# Canhbaochayrung.net
KiCad netlist of a schematic drawn in Altium Designer
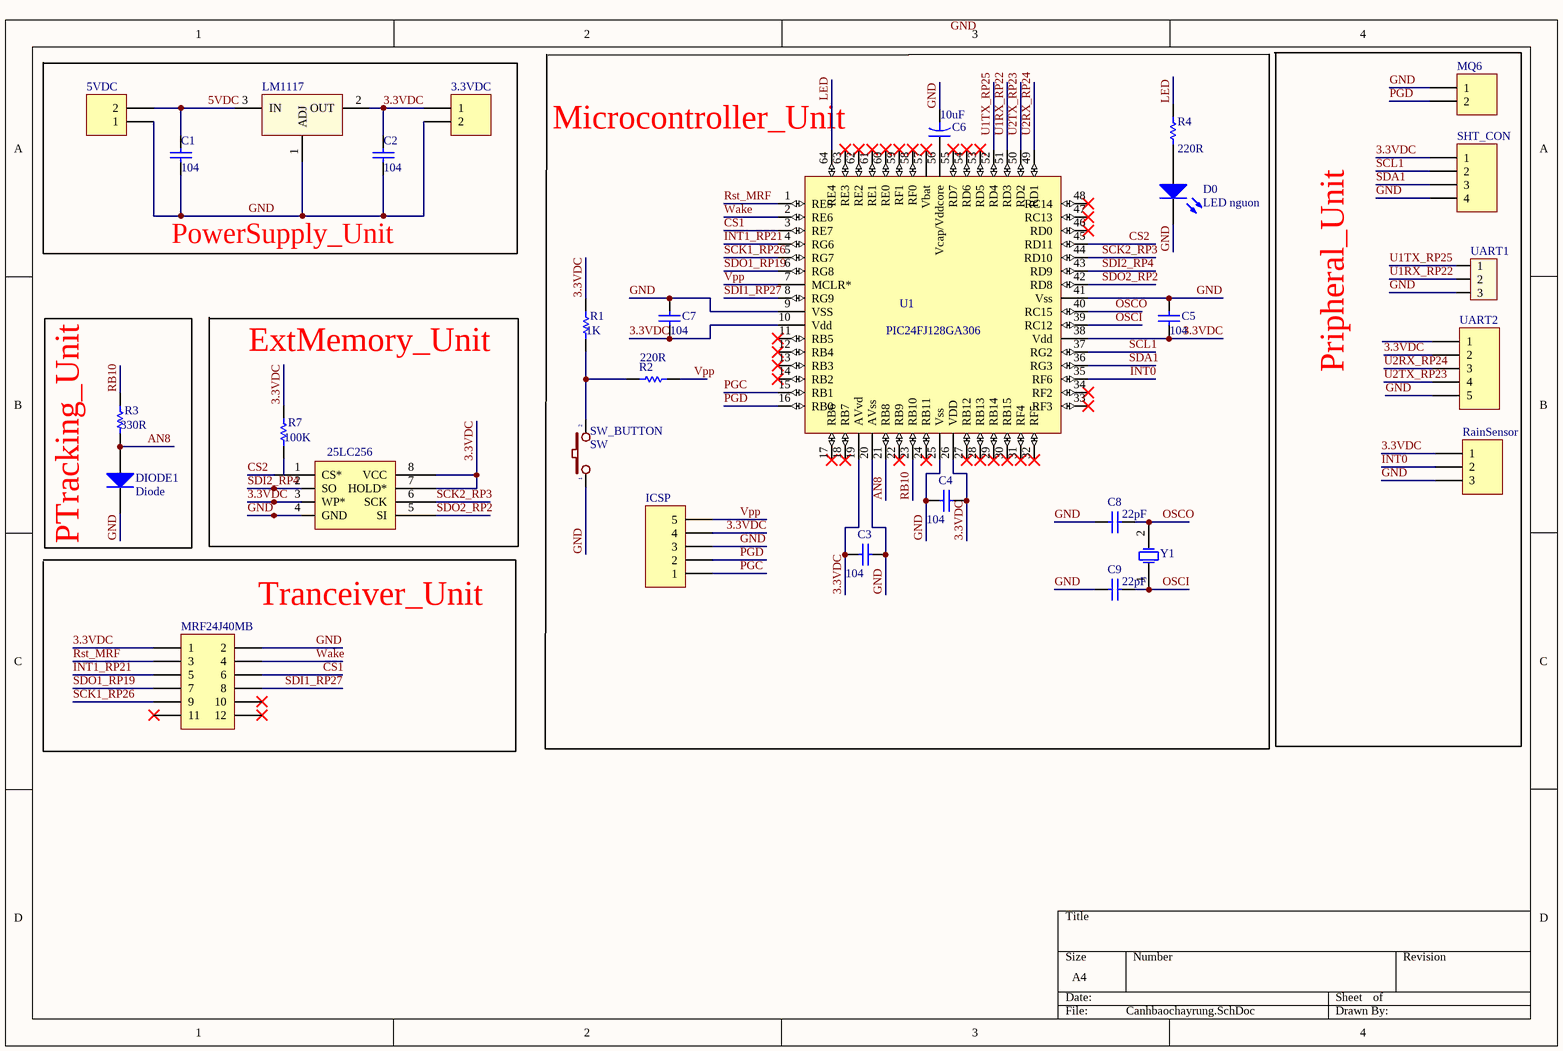
[diagram p0: Canhbaochayrung.SchDoc]

(export (version "E")
  (design (tool "Eeschema 10.0.6"))
  (components
    (comp (ref "3.3VDC")
      (value "Header 2")
      (footprint "HDR1X2")
      (description "Header, 2-Pin")
      (fields (field (name "PUBLISHER") "Altium Limited"))
      (libsource (lib "") (part "Header 2_1"))
    )
    (comp (ref "5VDC")
      (value "Header 2")
      (footprint "HDR1X2")
      (description "Header, 2-Pin")
      (fields (field (name "PUBLISHER") "Altium Limited"))
      (libsource (lib "Miscellaneous Connectors") (part "Header 2"))
    )
    (comp (ref "25LC256") (value "25LC256") (footprint "DIP-8") (libsource (lib "25LC256") (part "25LC256")))
    (comp (ref "C1")
      (value "104")
      (footprint "C0805")
      (description "Capacitor")
      (fields (field (name "Comment") "Cap") (field (name "PUBLISHER") "Altium Limited"))
      (libsource (lib "Miscellaneous Devices") (part "Cap"))
    )
    (comp (ref "C2")
      (value "104")
      (footprint "C0805")
      (description "Capacitor")
      (fields (field (name "Comment") "Cap") (field (name "PUBLISHER") "Altium Limited"))
      (libsource (lib "Miscellaneous Devices") (part "Cap"))
    )
    (comp (ref "C3")
      (value "104")
      (footprint "C0805")
      (description "Capacitor")
      (fields (field (name "Comment") "Cap") (field (name "PUBLISHER") "Altium Limited"))
      (libsource (lib "Miscellaneous Devices") (part "Cap"))
    )
    (comp (ref "C4")
      (value "104")
      (footprint "C0805")
      (description "Capacitor")
      (fields (field (name "Comment") "Cap") (field (name "PUBLISHER") "Altium Limited"))
      (libsource (lib "Miscellaneous Devices") (part "Cap"))
    )
    (comp (ref "C5")
      (value "104")
      (footprint "C0805")
      (description "Capacitor")
      (fields (field (name "Comment") "Cap") (field (name "PUBLISHER") "Altium Limited"))
      (libsource (lib "Miscellaneous Devices") (part "Cap"))
    )
    (comp (ref "C6")
      (value "10uF")
      (footprint "CAP P 6.3x5.4")
      (description "Capacitor")
      (fields (field (name "Comment") "Cap2") (field (name "PUBLISHER") "Altium Limited"))
      (libsource (lib "Miscellaneous Devices") (part "Cap2"))
    )
    (comp (ref "C7")
      (value "104")
      (footprint "C0805")
      (description "Capacitor")
      (fields (field (name "Comment") "Cap") (field (name "PUBLISHER") "Altium Limited"))
      (libsource (lib "Miscellaneous Devices") (part "Cap"))
    )
    (comp (ref "C8")
      (value "22pF")
      (footprint "SM-0805")
      (description "Capacitor")
      (fields (field (name "Comment") "Cap") (field (name "PUBLISHER") "Altium Limited"))
      (libsource (lib "Miscellaneous Devices") (part "Cap"))
    )
    (comp (ref "C9")
      (value "22pF")
      (footprint "SM-0805")
      (description "Capacitor")
      (fields (field (name "Comment") "Cap") (field (name "PUBLISHER") "Altium Limited"))
      (libsource (lib "Miscellaneous Devices") (part "Cap"))
    )
    (comp (ref "D0")
      (value "LED nguon")
      (footprint "LED3mm")
      (description "Typical INFRARED GaAs LED")
      (fields (field (name "PUBLISHER") "Altium Limited"))
      (libsource (lib "Miscellaneous Devices") (part "LED0"))
    )
    (comp (ref "DIODE1")
      (value "Diode")
      (footprint "DZ0.5A")
      (description "Default Diode")
      (fields (field (name "PUBLISHER") "Altium Limited"))
      (libsource (lib "Miscellaneous Devices") (part "Diode"))
    )
    (comp (ref "ICSP")
      (value "ICSP")
      (footprint "CON5")
      (description "Header, 5-Pin")
      (fields (field (name "PUBLISHER") "Altium Limited"))
      (libsource (lib "Miscellaneous Connectors") (part "Header 5"))
    )
    (comp (ref "LM1117")
      (value "LM317")
      (footprint "SOT223-4N")
      (description "Adj Voltage +1.2 -> +37V")
      (libsource (lib "syhaunguyen") (part "LM317"))
    )
    (comp (ref "MQ6")
      (value "MQ-6")
      (footprint "CON2")
      (description "Header, 2-Pin")
      (fields (field (name "PUBLISHER") "Altium Limited"))
      (libsource (lib "") (part "Header 2_1"))
    )
    (comp (ref "MRF24J40MB")
      (value "Header 6X2")
      (footprint "MRF24J40MB_board_mini")
      (description "Header, 6-Pin, Dual row")
      (fields (field (name "PUBLISHER") "Altium Limited"))
      (libsource (lib "Miscellaneous Connectors") (part "Header 6X2"))
    )
    (comp (ref "R1")
      (value "1K")
      (footprint "C0805")
      (description "Resistor")
      (fields (field (name "Comment") "Res1") (field (name "PUBLISHER") "Altium Limited"))
      (libsource (lib "Miscellaneous Devices") (part "Res1"))
    )
    (comp (ref "R2")
      (value "220R")
      (footprint "C0805")
      (description "Resistor")
      (fields (field (name "Comment") "res") (field (name "PUBLISHER") "Altium Limited"))
      (libsource (lib "Miscellaneous Devices") (part "Res1"))
    )
    (comp (ref "R3")
      (value "330R")
      (footprint "C0805")
      (description "Resistor")
      (fields (field (name "Comment") "Res1") (field (name "PUBLISHER") "Altium Limited"))
      (libsource (lib "Miscellaneous Devices") (part "Res1"))
    )
    (comp (ref "R4")
      (value "220R")
      (footprint "C0805")
      (description "Resistor")
      (fields (field (name "Comment") "Res1") (field (name "PUBLISHER") "Altium Limited"))
      (libsource (lib "Miscellaneous Devices") (part "Res1"))
    )
    (comp (ref "R7")
      (value "100K")
      (footprint "C0805")
      (description "Semiconductor Resistor")
      (fields (field (name "Comment") "Res Semi") (field (name "PUBLISHER") "Altium Limited"))
      (libsource (lib "Miscellaneous Devices") (part "Res Semi"))
    )
    (comp (ref "RainSensor")
      (value "PIR module")
      (footprint "CON3")
      (description "Header, 3-Pin, Right Angle")
      (fields (field (name "PUBLISHER") "Altium Limited"))
      (libsource (lib "Miscellaneous Connectors") (part "Header 3H"))
    )
    (comp (ref "SHT_CON")
      (value "SHT10 conector")
      (footprint "CON4")
      (description "Header, 4-Pin")
      (fields (field (name "PUBLISHER") "Altium Limited"))
      (libsource (lib "Miscellaneous Connectors") (part "Header 4"))
    )
    (comp (ref "SW_BUTTON")
      (value "SW")
      (footprint "SW-2P-S")
      (description "Switch button 2 pin")
      (libsource (lib "syhaunguyen") (part "SW2"))
    )
    (comp (ref "U1")
      (value "PIC24FJ128GA306")
      (footprint "TQFP-PT64_N")
      (libsource (lib "Mylibbrary") (part "PIC24FJ128GA306"))
    )
    (comp (ref "UART1")
      (value "UART1")
      (footprint "CON3")
      (description "Connector 3")
      (libsource (lib "syhaunguyen") (part "Con3"))
    )
    (comp (ref "UART2")
      (value "~")
      (footprint "HDR1X5")
      (description "Header, 5-Pin")
      (fields (field (name "PUBLISHER") "Altium Limited"))
      (libsource (lib "") (part "Header 5_1"))
    )
    (comp (ref "Y1")
      (value "XTAL")
      (footprint "XT2")
      (description "Crystal Oscillator")
      (fields (field (name "PUBLISHER") "Altium Limited"))
      (libsource (lib "Miscellaneous Devices") (part "XTAL"))
    )
  )
  (nets
    (net (code "1") (name "/3.3VDC") (class "Default")
      (node (ref "25LC256") (pin "3") (pinfunction "WP*_3") (pintype "passive"))
      (node (ref "25LC256") (pin "7") (pinfunction "HOLD*_7") (pintype "passive"))
      (node (ref "25LC256") (pin "8") (pinfunction "VCC_8") (pintype "power_in"))
      (node (ref "3.3VDC") (pin "1") (pinfunction "1_1") (pintype "passive"))
      (node (ref "C2") (pin "2") (pinfunction "2_2") (pintype "passive"))
      (node (ref "C3") (pin "1") (pinfunction "1_1") (pintype "passive"))
      (node (ref "C4") (pin "2") (pinfunction "2_2") (pintype "passive"))
      (node (ref "C5") (pin "1") (pinfunction "1_1") (pintype "passive"))
      (node (ref "C7") (pin "1") (pinfunction "1_1") (pintype "passive"))
      (node (ref "ICSP") (pin "4") (pinfunction "4_4") (pintype "passive"))
      (node (ref "LM1117") (pin "2") (pinfunction "OUT_2") (pintype "passive"))
      (node (ref "MRF24J40MB") (pin "1") (pinfunction "1_1") (pintype "passive"))
      (node (ref "R1") (pin "2") (pinfunction "2_2") (pintype "passive"))
      (node (ref "R7") (pin "2") (pinfunction "2_2") (pintype "passive"))
      (node (ref "RainSensor") (pin "1") (pinfunction "1_1") (pintype "passive"))
      (node (ref "SHT_CON") (pin "1") (pinfunction "1_1") (pintype "passive"))
      (node (ref "U1") (pin "10") (pinfunction "Vdd_10") (pintype "passive"))
      (node (ref "U1") (pin "19") (pinfunction "AVvd_19") (pintype "power_in"))
      (node (ref "U1") (pin "26") (pinfunction "VDD_26") (pintype "power_in"))
      (node (ref "U1") (pin "38") (pinfunction "Vdd_38") (pintype "power_in"))
      (node (ref "UART2") (pin "2") (pinfunction "2_2") (pintype "passive"))
    )
    (net (code "2") (name "/5VDC") (class "Default")
      (node (ref "5VDC") (pin "2") (pinfunction "2_2") (pintype "passive"))
      (node (ref "C1") (pin "2") (pinfunction "2_2") (pintype "passive"))
      (node (ref "LM1117") (pin "3") (pinfunction "IN_3") (pintype "passive"))
    )
    (net (code "3") (name "/AN8") (class "Default")
      (node (ref "DIODE1") (pin "1") (pinfunction "A_1") (pintype "passive"))
      (node (ref "R3") (pin "1") (pinfunction "1_1") (pintype "passive"))
      (node (ref "U1") (pin "21") (pinfunction "RB8_21") (pintype "bidirectional"))
    )
    (net (code "4") (name "/CS1") (class "Default")
      (node (ref "MRF24J40MB") (pin "6") (pinfunction "6_6") (pintype "passive"))
      (node (ref "U1") (pin "3") (pinfunction "RE7_3") (pintype "bidirectional"))
    )
    (net (code "5") (name "/CS2") (class "Default")
      (node (ref "25LC256") (pin "1") (pinfunction "CS*_1") (pintype "passive"))
      (node (ref "U1") (pin "45") (pinfunction "RD11_45") (pintype "bidirectional"))
    )
    (net (code "6") (name "/GND") (class "Default")
      (node (ref "25LC256") (pin "4") (pinfunction "GND_4") (pintype "power_in"))
      (node (ref "3.3VDC") (pin "2") (pinfunction "2_2") (pintype "passive"))
      (node (ref "5VDC") (pin "1") (pinfunction "1_1") (pintype "passive"))
      (node (ref "C1") (pin "1") (pinfunction "1_1") (pintype "passive"))
      (node (ref "C2") (pin "1") (pinfunction "1_1") (pintype "passive"))
      (node (ref "C3") (pin "2") (pinfunction "2_2") (pintype "passive"))
      (node (ref "C4") (pin "1") (pinfunction "1_1") (pintype "passive"))
      (node (ref "C5") (pin "2") (pinfunction "2_2") (pintype "passive"))
      (node (ref "C6") (pin "2") (pinfunction "2_2") (pintype "passive"))
      (node (ref "C7") (pin "2") (pinfunction "2_2") (pintype "passive"))
      (node (ref "C8") (pin "1") (pinfunction "1_1") (pintype "passive"))
      (node (ref "C9") (pin "1") (pinfunction "1_1") (pintype "passive"))
      (node (ref "D0") (pin "2") (pinfunction "K_2") (pintype "passive"))
      (node (ref "DIODE1") (pin "2") (pinfunction "K_2") (pintype "passive"))
      (node (ref "ICSP") (pin "3") (pinfunction "3_3") (pintype "passive"))
      (node (ref "LM1117") (pin "1") (pinfunction "ADJ_1") (pintype "passive"))
      (node (ref "MQ6") (pin "1") (pinfunction "1_1") (pintype "passive"))
      (node (ref "MRF24J40MB") (pin "2") (pinfunction "2_2") (pintype "passive"))
      (node (ref "RainSensor") (pin "3") (pinfunction "3_3") (pintype "passive"))
      (node (ref "SHT_CON") (pin "4") (pinfunction "4_4") (pintype "passive"))
      (node (ref "SW_BUTTON") (pin "1") (pinfunction "1_1") (pintype "passive"))
      (node (ref "U1") (pin "20") (pinfunction "AVss_20") (pintype "power_in"))
      (node (ref "U1") (pin "25") (pinfunction "Vss_25") (pintype "power_in"))
      (node (ref "U1") (pin "41") (pinfunction "Vss_41") (pintype "power_in"))
      (node (ref "U1") (pin "9") (pinfunction "VSS_9") (pintype "power_in"))
      (node (ref "UART1") (pin "3") (pinfunction "3_3") (pintype "passive"))
      (node (ref "UART2") (pin "5") (pinfunction "5_5") (pintype "passive"))
    )
    (net (code "7") (name "/INT0") (class "Default")
      (node (ref "RainSensor") (pin "2") (pinfunction "2_2") (pintype "passive"))
      (node (ref "U1") (pin "35") (pinfunction "RF6_35") (pintype "bidirectional"))
    )
    (net (code "8") (name "/INT1_RP21") (class "Default")
      (node (ref "MRF24J40MB") (pin "5") (pinfunction "5_5") (pintype "passive"))
      (node (ref "U1") (pin "4") (pinfunction "RG6_4") (pintype "bidirectional"))
    )
    (net (code "9") (name "/LED") (class "Default")
      (node (ref "R4") (pin "2") (pinfunction "2_2") (pintype "passive"))
      (node (ref "U1") (pin "64") (pinfunction "RE4_64") (pintype "bidirectional"))
    )
    (net (code "10") (name "/OSCI") (class "Default")
      (node (ref "C9") (pin "2") (pinfunction "2_2") (pintype "passive"))
      (node (ref "U1") (pin "39") (pinfunction "RC12_39") (pintype "bidirectional"))
      (node (ref "Y1") (pin "1") (pinfunction "OSC1_1") (pintype "passive"))
    )
    (net (code "11") (name "/OSCO") (class "Default")
      (node (ref "C8") (pin "2") (pinfunction "2_2") (pintype "passive"))
      (node (ref "U1") (pin "40") (pinfunction "RC15_40") (pintype "bidirectional"))
      (node (ref "Y1") (pin "2") (pinfunction "OSC2_2") (pintype "passive"))
    )
    (net (code "12") (name "/PGC") (class "Default")
      (node (ref "ICSP") (pin "1") (pinfunction "1_1") (pintype "passive"))
      (node (ref "U1") (pin "15") (pinfunction "RB1_15") (pintype "bidirectional"))
    )
    (net (code "13") (name "/PGD") (class "Default")
      (node (ref "ICSP") (pin "2") (pinfunction "2_2") (pintype "passive"))
      (node (ref "MQ6") (pin "2") (pinfunction "2_2") (pintype "passive"))
      (node (ref "U1") (pin "16") (pinfunction "RB0_16") (pintype "bidirectional"))
    )
    (net (code "14") (name "/RB10") (class "Default")
      (node (ref "R3") (pin "2") (pinfunction "2_2") (pintype "passive"))
      (node (ref "U1") (pin "23") (pinfunction "RB10_23") (pintype "bidirectional"))
    )
    (net (code "15") (name "/Rst_MRF") (class "Default")
      (node (ref "MRF24J40MB") (pin "3") (pinfunction "3_3") (pintype "passive"))
      (node (ref "U1") (pin "1") (pinfunction "RE5_1") (pintype "bidirectional"))
    )
    (net (code "16") (name "/SCK1_RP26") (class "Default")
      (node (ref "MRF24J40MB") (pin "9") (pinfunction "9_9") (pintype "passive"))
      (node (ref "U1") (pin "5") (pinfunction "RG7_5") (pintype "bidirectional"))
    )
    (net (code "17") (name "/SCK2_RP3") (class "Default")
      (node (ref "25LC256") (pin "6") (pinfunction "SCK_6") (pintype "passive"))
      (node (ref "U1") (pin "44") (pinfunction "RD10_44") (pintype "bidirectional"))
    )
    (net (code "18") (name "/SCL1") (class "Default")
      (node (ref "SHT_CON") (pin "2") (pinfunction "2_2") (pintype "passive"))
      (node (ref "U1") (pin "37") (pinfunction "RG2_37") (pintype "bidirectional"))
    )
    (net (code "19") (name "/SDA1") (class "Default")
      (node (ref "SHT_CON") (pin "3") (pinfunction "3_3") (pintype "passive"))
      (node (ref "U1") (pin "36") (pinfunction "RG3_36") (pintype "bidirectional"))
    )
    (net (code "20") (name "/SDI1_RP27") (class "Default")
      (node (ref "MRF24J40MB") (pin "8") (pinfunction "8_8") (pintype "passive"))
      (node (ref "U1") (pin "8") (pinfunction "RG9_8") (pintype "bidirectional"))
    )
    (net (code "21") (name "/SDI2_RP4") (class "Default")
      (node (ref "25LC256") (pin "2") (pinfunction "SO_2") (pintype "passive"))
      (node (ref "U1") (pin "43") (pinfunction "RD9_43") (pintype "bidirectional"))
    )
    (net (code "22") (name "/SDO1_RP19") (class "Default")
      (node (ref "MRF24J40MB") (pin "7") (pinfunction "7_7") (pintype "passive"))
      (node (ref "U1") (pin "6") (pinfunction "RG8_6") (pintype "bidirectional"))
    )
    (net (code "23") (name "/SDO2_RP2") (class "Default")
      (node (ref "25LC256") (pin "5") (pinfunction "SI_5") (pintype "passive"))
      (node (ref "U1") (pin "42") (pinfunction "RD8_42") (pintype "bidirectional"))
    )
    (net (code "24") (name "/U1RX_RP22") (class "Default")
      (node (ref "U1") (pin "51") (pinfunction "RD3_51") (pintype "bidirectional"))
      (node (ref "UART1") (pin "2") (pinfunction "2_2") (pintype "passive"))
    )
    (net (code "25") (name "/U1TX_RP25") (class "Default")
      (node (ref "U1") (pin "52") (pinfunction "RD4_52") (pintype "bidirectional"))
      (node (ref "UART1") (pin "1") (pinfunction "1_1") (pintype "passive"))
    )
    (net (code "26") (name "/U2RX_RP24") (class "Default")
      (node (ref "U1") (pin "49") (pinfunction "RD1_49") (pintype "bidirectional"))
      (node (ref "UART2") (pin "3") (pinfunction "3_3") (pintype "passive"))
    )
    (net (code "27") (name "/U2TX_RP23") (class "Default")
      (node (ref "U1") (pin "50") (pinfunction "RD2_50") (pintype "bidirectional"))
      (node (ref "UART2") (pin "4") (pinfunction "4_4") (pintype "passive"))
    )
    (net (code "28") (name "/Vpp") (class "Default")
      (node (ref "ICSP") (pin "5") (pinfunction "5_5") (pintype "passive"))
      (node (ref "R2") (pin "2") (pinfunction "2_2") (pintype "passive"))
      (node (ref "U1") (pin "7") (pinfunction "MCLR*_7") (pintype "passive"))
    )
    (net (code "29") (name "/Wake") (class "Default")
      (node (ref "MRF24J40MB") (pin "4") (pinfunction "4_4") (pintype "passive"))
      (node (ref "U1") (pin "2") (pinfunction "RE6_2") (pintype "bidirectional"))
    )
    (net (code "30") (name "Net-(D0-A)") (class "Default")
      (node (ref "D0") (pin "1") (pinfunction "A_1") (pintype "passive"))
      (node (ref "R4") (pin "1") (pinfunction "1_1") (pintype "passive"))
    )
    (net (code "31") (name "Net-(R1-Pad1)") (class "Default")
      (node (ref "R1") (pin "1") (pinfunction "1_1") (pintype "passive"))
      (node (ref "R2") (pin "1") (pinfunction "1_1") (pintype "passive"))
      (node (ref "SW_BUTTON") (pin "2") (pinfunction "2_2") (pintype "passive"))
    )
    (net (code "32") (name "Net-(U1-Vcap{slash}Vddcore)") (class "Default")
      (node (ref "C6") (pin "1") (pinfunction "1_1") (pintype "passive"))
      (node (ref "U1") (pin "56") (pinfunction "Vcap/Vddcore_56") (pintype "power_in"))
    )
    (net (code "33") (name "unconnected-(MRF24J40MB-Pad10)") (class "Default")
      (node (ref "MRF24J40MB") (pin "10") (pinfunction "10_10") (pintype "passive+no_connect"))
    )
    (net (code "34") (name "unconnected-(MRF24J40MB-Pad11)") (class "Default")
      (node (ref "MRF24J40MB") (pin "11") (pinfunction "11_11") (pintype "passive+no_connect"))
    )
    (net (code "35") (name "unconnected-(MRF24J40MB-Pad12)") (class "Default")
      (node (ref "MRF24J40MB") (pin "12") (pinfunction "12_12") (pintype "passive+no_connect"))
    )
    (net (code "36") (name "unconnected-(R7-Pad1)") (class "Default")
      (node (ref "R7") (pin "1") (pinfunction "1_1") (pintype "passive"))
    )
    (net (code "37") (name "unconnected-(U1-RB2-Pad14)") (class "Default")
      (node (ref "U1") (pin "14") (pinfunction "RB2_14") (pintype "bidirectional+no_connect"))
    )
    (net (code "38") (name "unconnected-(U1-RB3-Pad13)") (class "Default")
      (node (ref "U1") (pin "13") (pinfunction "RB3_13") (pintype "bidirectional+no_connect"))
    )
    (net (code "39") (name "unconnected-(U1-RB4-Pad12)") (class "Default")
      (node (ref "U1") (pin "12") (pinfunction "RB4_12") (pintype "bidirectional+no_connect"))
    )
    (net (code "40") (name "unconnected-(U1-RB5-Pad11)") (class "Default")
      (node (ref "U1") (pin "11") (pinfunction "RB5_11") (pintype "bidirectional+no_connect"))
    )
    (net (code "41") (name "unconnected-(U1-RB6-Pad17)") (class "Default")
      (node (ref "U1") (pin "17") (pinfunction "RB6_17") (pintype "bidirectional+no_connect"))
    )
    (net (code "42") (name "unconnected-(U1-RB7-Pad18)") (class "Default")
      (node (ref "U1") (pin "18") (pinfunction "RB7_18") (pintype "bidirectional+no_connect"))
    )
    (net (code "43") (name "unconnected-(U1-RB9-Pad22)") (class "Default")
      (node (ref "U1") (pin "22") (pinfunction "RB9_22") (pintype "bidirectional+no_connect"))
    )
    (net (code "44") (name "unconnected-(U1-RB11-Pad24)") (class "Default")
      (node (ref "U1") (pin "24") (pinfunction "RB11_24") (pintype "bidirectional+no_connect"))
    )
    (net (code "45") (name "unconnected-(U1-RB12-Pad27)") (class "Default")
      (node (ref "U1") (pin "27") (pinfunction "RB12_27") (pintype "bidirectional+no_connect"))
    )
    (net (code "46") (name "unconnected-(U1-RB13-Pad28)") (class "Default")
      (node (ref "U1") (pin "28") (pinfunction "RB13_28") (pintype "bidirectional+no_connect"))
    )
    (net (code "47") (name "unconnected-(U1-RB14-Pad29)") (class "Default")
      (node (ref "U1") (pin "29") (pinfunction "RB14_29") (pintype "bidirectional+no_connect"))
    )
    (net (code "48") (name "unconnected-(U1-RB15-Pad30)") (class "Default")
      (node (ref "U1") (pin "30") (pinfunction "RB15_30") (pintype "bidirectional+no_connect"))
    )
    (net (code "49") (name "unconnected-(U1-RC13-Pad47)") (class "Default")
      (node (ref "U1") (pin "47") (pinfunction "RC13_47") (pintype "bidirectional+no_connect"))
    )
    (net (code "50") (name "unconnected-(U1-RC14-Pad48)") (class "Default")
      (node (ref "U1") (pin "48") (pinfunction "RC14_48") (pintype "bidirectional+no_connect"))
    )
    (net (code "51") (name "unconnected-(U1-RD0-Pad46)") (class "Default")
      (node (ref "U1") (pin "46") (pinfunction "RD0_46") (pintype "bidirectional+no_connect"))
    )
    (net (code "52") (name "unconnected-(U1-RD5-Pad53)") (class "Default")
      (node (ref "U1") (pin "53") (pinfunction "RD5_53") (pintype "bidirectional+no_connect"))
    )
    (net (code "53") (name "unconnected-(U1-RD6-Pad54)") (class "Default")
      (node (ref "U1") (pin "54") (pinfunction "RD6_54") (pintype "bidirectional+no_connect"))
    )
    (net (code "54") (name "unconnected-(U1-RD7-Pad55)") (class "Default")
      (node (ref "U1") (pin "55") (pinfunction "RD7_55") (pintype "bidirectional+no_connect"))
    )
    (net (code "55") (name "unconnected-(U1-RE0-Pad60)") (class "Default")
      (node (ref "U1") (pin "60") (pinfunction "RE0_60") (pintype "bidirectional+no_connect"))
    )
    (net (code "56") (name "unconnected-(U1-RE1-Pad61)") (class "Default")
      (node (ref "U1") (pin "61") (pinfunction "RE1_61") (pintype "bidirectional+no_connect"))
    )
    (net (code "57") (name "unconnected-(U1-RE2-Pad62)") (class "Default")
      (node (ref "U1") (pin "62") (pinfunction "RE2_62") (pintype "bidirectional+no_connect"))
    )
    (net (code "58") (name "unconnected-(U1-RE3-Pad63)") (class "Default")
      (node (ref "U1") (pin "63") (pinfunction "RE3_63") (pintype "bidirectional+no_connect"))
    )
    (net (code "59") (name "unconnected-(U1-RF0-Pad58)") (class "Default")
      (node (ref "U1") (pin "58") (pinfunction "RF0_58") (pintype "bidirectional+no_connect"))
    )
    (net (code "60") (name "unconnected-(U1-RF1-Pad59)") (class "Default")
      (node (ref "U1") (pin "59") (pinfunction "RF1_59") (pintype "bidirectional+no_connect"))
    )
    (net (code "61") (name "unconnected-(U1-RF2-Pad34)") (class "Default")
      (node (ref "U1") (pin "34") (pinfunction "RF2_34") (pintype "bidirectional+no_connect"))
    )
    (net (code "62") (name "unconnected-(U1-RF3-Pad33)") (class "Default")
      (node (ref "U1") (pin "33") (pinfunction "RF3_33") (pintype "bidirectional+no_connect"))
    )
    (net (code "63") (name "unconnected-(U1-RF4-Pad31)") (class "Default")
      (node (ref "U1") (pin "31") (pinfunction "RF4_31") (pintype "bidirectional+no_connect"))
    )
    (net (code "64") (name "unconnected-(U1-RF5-Pad32)") (class "Default")
      (node (ref "U1") (pin "32") (pinfunction "RF5_32") (pintype "bidirectional+no_connect"))
    )
    (net (code "65") (name "unconnected-(U1-Vbat-Pad57)") (class "Default")
      (node (ref "U1") (pin "57") (pinfunction "Vbat_57") (pintype "power_in+no_connect"))
    )
    (net (code "66") (name "unconnected-(UART2-Pad1)") (class "Default")
      (node (ref "UART2") (pin "1") (pinfunction "1_1") (pintype "passive"))
    )
  )
)
